# Main.net
KiCad netlist of a schematic drawn in Altium Designer
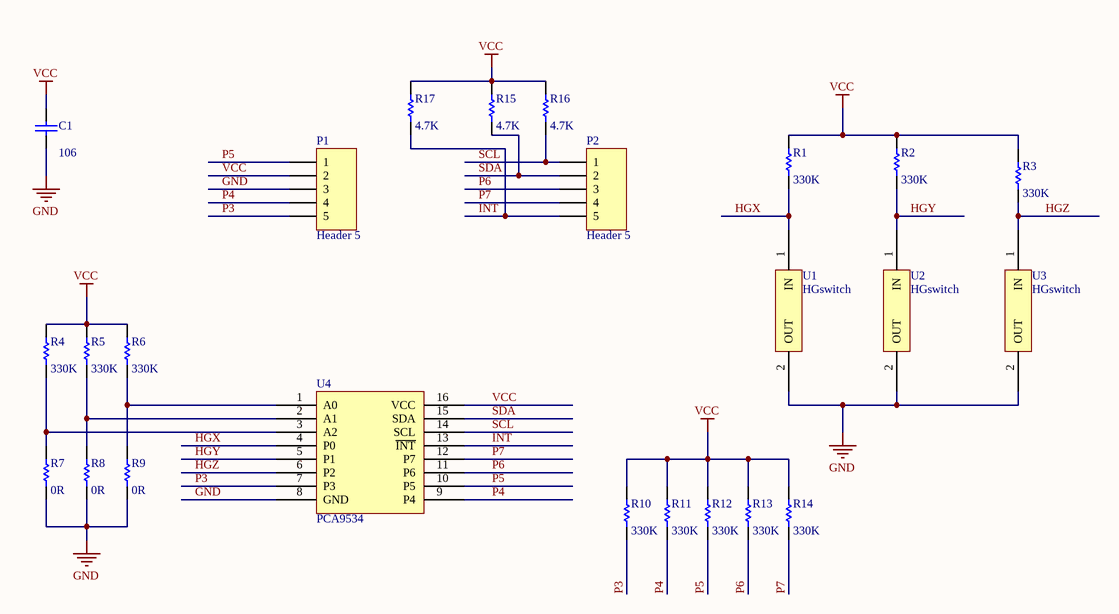
[diagram p0: Main.SchDoc]

(export (version "E")
  (design (tool "Eeschema 10.0.6"))
  (components
    (comp (ref "C1")
      (value "106")
      (footprint "0603C")
      (description "Capacitor")
      (fields (field (name "PUBLISHER") "Altium Limited"))
      (libsource (lib "Miscellaneous Devices") (part "Cap"))
    )
    (comp (ref "P1")
      (value "Header 5")
      (footprint "HDR1X5")
      (description "Header, 5-Pin")
      (fields (field (name "PUBLISHER") "Altium Limited"))
      (libsource (lib "Miscellaneous Connectors") (part "Header 5"))
    )
    (comp (ref "P2")
      (value "Header 5")
      (footprint "HDR1X5")
      (description "Header, 5-Pin")
      (fields (field (name "PUBLISHER") "Altium Limited"))
      (libsource (lib "Miscellaneous Connectors") (part "Header 5"))
    )
    (comp (ref "R1")
      (value "330K")
      (footprint "0603R")
      (description "Resistor")
      (fields (field (name "Comment") "Res1") (field (name "PUBLISHER") "Altium Limited"))
      (libsource (lib "Miscellaneous Devices") (part "Res1"))
    )
    (comp (ref "R2")
      (value "330K")
      (footprint "0603R")
      (description "Resistor")
      (fields (field (name "Comment") "Res1") (field (name "PUBLISHER") "Altium Limited"))
      (libsource (lib "Miscellaneous Devices") (part "Res1"))
    )
    (comp (ref "R3")
      (value "330K")
      (footprint "0603R")
      (description "Resistor")
      (fields (field (name "Comment") "Res1") (field (name "PUBLISHER") "Altium Limited"))
      (libsource (lib "Miscellaneous Devices") (part "Res1"))
    )
    (comp (ref "R4")
      (value "330K")
      (footprint "0603R")
      (description "Resistor")
      (fields (field (name "Comment") "Res1") (field (name "PUBLISHER") "Altium Limited"))
      (libsource (lib "Miscellaneous Devices") (part "Res1"))
    )
    (comp (ref "R5")
      (value "330K")
      (footprint "0603R")
      (description "Resistor")
      (fields (field (name "Comment") "Res1") (field (name "PUBLISHER") "Altium Limited"))
      (libsource (lib "Miscellaneous Devices") (part "Res1"))
    )
    (comp (ref "R6")
      (value "330K")
      (footprint "0603R")
      (description "Resistor")
      (fields (field (name "Comment") "Res1") (field (name "PUBLISHER") "Altium Limited"))
      (libsource (lib "Miscellaneous Devices") (part "Res1"))
    )
    (comp (ref "R7")
      (value "0R")
      (footprint "0603R")
      (description "Resistor")
      (fields (field (name "Comment") "Res1") (field (name "PUBLISHER") "Altium Limited"))
      (libsource (lib "Miscellaneous Devices") (part "Res1"))
    )
    (comp (ref "R8")
      (value "0R")
      (footprint "0603R")
      (description "Resistor")
      (fields (field (name "Comment") "Res1") (field (name "PUBLISHER") "Altium Limited"))
      (libsource (lib "Miscellaneous Devices") (part "Res1"))
    )
    (comp (ref "R9")
      (value "0R")
      (footprint "0603R")
      (description "Resistor")
      (fields (field (name "Comment") "Res1") (field (name "PUBLISHER") "Altium Limited"))
      (libsource (lib "Miscellaneous Devices") (part "Res1"))
    )
    (comp (ref "R10")
      (value "330K")
      (footprint "0603R")
      (description "Resistor")
      (fields (field (name "Comment") "Res1") (field (name "PUBLISHER") "Altium Limited"))
      (libsource (lib "Miscellaneous Devices") (part "Res1"))
    )
    (comp (ref "R11")
      (value "330K")
      (footprint "0603R")
      (description "Resistor")
      (fields (field (name "Comment") "Res1") (field (name "PUBLISHER") "Altium Limited"))
      (libsource (lib "Miscellaneous Devices") (part "Res1"))
    )
    (comp (ref "R12")
      (value "330K")
      (footprint "0603R")
      (description "Resistor")
      (fields (field (name "Comment") "Res1") (field (name "PUBLISHER") "Altium Limited"))
      (libsource (lib "Miscellaneous Devices") (part "Res1"))
    )
    (comp (ref "R13")
      (value "330K")
      (footprint "0603R")
      (description "Resistor")
      (fields (field (name "Comment") "Res1") (field (name "PUBLISHER") "Altium Limited"))
      (libsource (lib "Miscellaneous Devices") (part "Res1"))
    )
    (comp (ref "R14")
      (value "330K")
      (footprint "0603R")
      (description "Resistor")
      (fields (field (name "Comment") "Res1") (field (name "PUBLISHER") "Altium Limited"))
      (libsource (lib "Miscellaneous Devices") (part "Res1"))
    )
    (comp (ref "R15")
      (value "4.7K")
      (footprint "0603R")
      (description "Resistor")
      (fields (field (name "Comment") "Res1") (field (name "PUBLISHER") "Altium Limited"))
      (libsource (lib "Miscellaneous Devices") (part "Res1"))
    )
    (comp (ref "R16")
      (value "4.7K")
      (footprint "0603R")
      (description "Resistor")
      (fields (field (name "Comment") "Res1") (field (name "PUBLISHER") "Altium Limited"))
      (libsource (lib "Miscellaneous Devices") (part "Res1"))
    )
    (comp (ref "R17")
      (value "4.7K")
      (footprint "0603R")
      (description "Resistor")
      (fields (field (name "Comment") "Res1") (field (name "PUBLISHER") "Altium Limited"))
      (libsource (lib "Miscellaneous Devices") (part "Res1"))
    )
    (comp (ref "U1") (value "HGswitch") (footprint "HG-H") (libsource (lib "bias_sensor") (part "HGswitch")))
    (comp (ref "U2") (value "HGswitch") (footprint "HG-H") (libsource (lib "bias_sensor") (part "HGswitch")))
    (comp (ref "U3") (value "HGswitch") (footprint "HG-V") (libsource (lib "bias_sensor") (part "HGswitch")))
    (comp (ref "U4") (value "PCA9534") (footprint "TSSOP16") (libsource (lib "bias_sensor") (part "PCA9534")))
  )
  (nets
    (net (code "1") (name "/HGX") (class "Default")
      (node (ref "R1") (pin "1") (pinfunction "1_1") (pintype "passive"))
      (node (ref "U1") (pin "1") (pinfunction "IN_1") (pintype "passive"))
      (node (ref "U4") (pin "4") (pinfunction "P0_4") (pintype "passive"))
    )
    (net (code "2") (name "/HGY") (class "Default")
      (node (ref "R2") (pin "1") (pinfunction "1_1") (pintype "passive"))
      (node (ref "U2") (pin "1") (pinfunction "IN_1") (pintype "passive"))
      (node (ref "U4") (pin "5") (pinfunction "P1_5") (pintype "passive"))
    )
    (net (code "3") (name "/HGZ") (class "Default")
      (node (ref "R3") (pin "1") (pinfunction "1_1") (pintype "passive"))
      (node (ref "U3") (pin "1") (pinfunction "IN_1") (pintype "passive"))
      (node (ref "U4") (pin "6") (pinfunction "P2_6") (pintype "passive"))
    )
    (net (code "4") (name "/INT") (class "Default")
      (node (ref "P2") (pin "5") (pinfunction "5_5") (pintype "passive"))
      (node (ref "R17") (pin "1") (pinfunction "1_1") (pintype "passive"))
      (node (ref "U4") (pin "13") (pinfunction "~{INT}_13") (pintype "passive"))
    )
    (net (code "5") (name "/P3") (class "Default")
      (node (ref "P1") (pin "5") (pinfunction "5_5") (pintype "passive"))
      (node (ref "R10") (pin "1") (pinfunction "1_1") (pintype "passive"))
      (node (ref "U4") (pin "7") (pinfunction "P3_7") (pintype "passive"))
    )
    (net (code "6") (name "/P4") (class "Default")
      (node (ref "P1") (pin "4") (pinfunction "4_4") (pintype "passive"))
      (node (ref "R11") (pin "1") (pinfunction "1_1") (pintype "passive"))
      (node (ref "U4") (pin "9") (pinfunction "P4_9") (pintype "passive"))
    )
    (net (code "7") (name "/P5") (class "Default")
      (node (ref "P1") (pin "1") (pinfunction "1_1") (pintype "passive"))
      (node (ref "R12") (pin "1") (pinfunction "1_1") (pintype "passive"))
      (node (ref "U4") (pin "10") (pinfunction "P5_10") (pintype "passive"))
    )
    (net (code "8") (name "/P6") (class "Default")
      (node (ref "P2") (pin "3") (pinfunction "3_3") (pintype "passive"))
      (node (ref "R13") (pin "1") (pinfunction "1_1") (pintype "passive"))
      (node (ref "U4") (pin "11") (pinfunction "P6_11") (pintype "passive"))
    )
    (net (code "9") (name "/P7") (class "Default")
      (node (ref "P2") (pin "4") (pinfunction "4_4") (pintype "passive"))
      (node (ref "R14") (pin "1") (pinfunction "1_1") (pintype "passive"))
      (node (ref "U4") (pin "12") (pinfunction "P7_12") (pintype "passive"))
    )
    (net (code "10") (name "/SCL") (class "Default")
      (node (ref "P2") (pin "1") (pinfunction "1_1") (pintype "passive"))
      (node (ref "R16") (pin "1") (pinfunction "1_1") (pintype "passive"))
      (node (ref "U4") (pin "14") (pinfunction "SCL_14") (pintype "passive"))
    )
    (net (code "11") (name "/SDA") (class "Default")
      (node (ref "P2") (pin "2") (pinfunction "2_2") (pintype "passive"))
      (node (ref "R15") (pin "1") (pinfunction "1_1") (pintype "passive"))
      (node (ref "U4") (pin "15") (pinfunction "SDA_15") (pintype "passive"))
    )
    (net (code "12") (name "GND") (class "Default")
      (node (ref "C1") (pin "1") (pinfunction "1_1") (pintype "passive"))
      (node (ref "P1") (pin "3") (pinfunction "3_3") (pintype "passive"))
      (node (ref "R7") (pin "1") (pinfunction "1_1") (pintype "passive"))
      (node (ref "R8") (pin "1") (pinfunction "1_1") (pintype "passive"))
      (node (ref "R9") (pin "1") (pinfunction "1_1") (pintype "passive"))
      (node (ref "U1") (pin "2") (pinfunction "OUT_2") (pintype "passive"))
      (node (ref "U2") (pin "2") (pinfunction "OUT_2") (pintype "passive"))
      (node (ref "U3") (pin "2") (pinfunction "OUT_2") (pintype "passive"))
      (node (ref "U4") (pin "8") (pinfunction "GND_8") (pintype "passive"))
    )
    (net (code "13") (name "Net-(U4-A0)") (class "Default")
      (node (ref "R6") (pin "1") (pinfunction "1_1") (pintype "passive"))
      (node (ref "R9") (pin "2") (pinfunction "2_2") (pintype "passive"))
      (node (ref "U4") (pin "1") (pinfunction "A0_1") (pintype "passive"))
    )
    (net (code "14") (name "Net-(U4-A1)") (class "Default")
      (node (ref "R5") (pin "1") (pinfunction "1_1") (pintype "passive"))
      (node (ref "R8") (pin "2") (pinfunction "2_2") (pintype "passive"))
      (node (ref "U4") (pin "2") (pinfunction "A1_2") (pintype "passive"))
    )
    (net (code "15") (name "Net-(U4-A2)") (class "Default")
      (node (ref "R4") (pin "1") (pinfunction "1_1") (pintype "passive"))
      (node (ref "R7") (pin "2") (pinfunction "2_2") (pintype "passive"))
      (node (ref "U4") (pin "3") (pinfunction "A2_3") (pintype "passive"))
    )
    (net (code "16") (name "VCC") (class "Default")
      (node (ref "C1") (pin "2") (pinfunction "2_2") (pintype "passive"))
      (node (ref "P1") (pin "2") (pinfunction "2_2") (pintype "passive"))
      (node (ref "R1") (pin "2") (pinfunction "2_2") (pintype "passive"))
      (node (ref "R10") (pin "2") (pinfunction "2_2") (pintype "passive"))
      (node (ref "R11") (pin "2") (pinfunction "2_2") (pintype "passive"))
      (node (ref "R12") (pin "2") (pinfunction "2_2") (pintype "passive"))
      (node (ref "R13") (pin "2") (pinfunction "2_2") (pintype "passive"))
      (node (ref "R14") (pin "2") (pinfunction "2_2") (pintype "passive"))
      (node (ref "R15") (pin "2") (pinfunction "2_2") (pintype "passive"))
      (node (ref "R16") (pin "2") (pinfunction "2_2") (pintype "passive"))
      (node (ref "R17") (pin "2") (pinfunction "2_2") (pintype "passive"))
      (node (ref "R2") (pin "2") (pinfunction "2_2") (pintype "passive"))
      (node (ref "R3") (pin "2") (pinfunction "2_2") (pintype "passive"))
      (node (ref "R4") (pin "2") (pinfunction "2_2") (pintype "passive"))
      (node (ref "R5") (pin "2") (pinfunction "2_2") (pintype "passive"))
      (node (ref "R6") (pin "2") (pinfunction "2_2") (pintype "passive"))
      (node (ref "U4") (pin "16") (pinfunction "VCC_16") (pintype "passive"))
    )
  )
)
